# pca9306_9dof.net
KiCad netlist of a schematic drawn in EAGLE
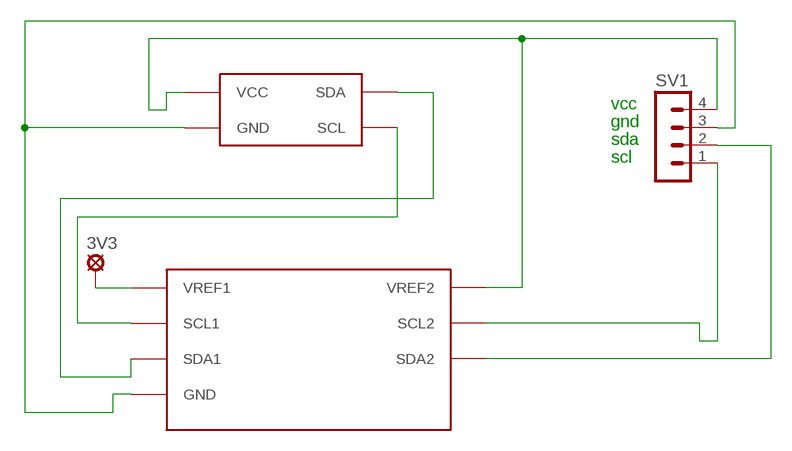
[diagram p0: schematic, sheet 1]

(export (version "E")
  (design (tool "Eeschema 10.0.6"))
  (components
    (comp (ref "3V3")
      (value "LSP11")
      (footprint "eagle-import:LSP11")
      (libsource (lib "eagle-import") (part "LSP11"))
    )
    (comp (ref "SV1")
      (value "MA04-1")
      (footprint "eagle-import:MA04-1")
      (libsource (lib "eagle-import") (part "MA04-1"))
    )
    (comp (ref "U$1")
      (value "PCA9306")
      (footprint "eagle-import:PCA9306")
      (libsource (lib "eagle-import") (part "PCA9306"))
    )
    (comp (ref "U$2")
      (value "9DOF")
      (footprint "eagle-import:9DOF")
      (libsource (lib "eagle-import") (part "9DOF"))
    )
  )
  (nets
    (net (code "1") (name "Net-(3V3-PadMP)") (class "Default")
      (node (ref "3V3") (pin "MP") (pinfunction "MP_MP") (pintype "passive"))
      (node (ref "U$1") (pin "VREF1") (pinfunction "VREF1_VREF1") (pintype "bidirectional"))
    )
    (net (code "2") (name "Net-(SV1-Pad1)") (class "Default")
      (node (ref "SV1") (pin "1") (pinfunction "1_1") (pintype "passive"))
      (node (ref "U$1") (pin "SCL2") (pinfunction "SCL2_SCL2") (pintype "bidirectional"))
    )
    (net (code "3") (name "Net-(SV1-Pad2)") (class "Default")
      (node (ref "SV1") (pin "2") (pinfunction "2_2") (pintype "passive"))
      (node (ref "U$1") (pin "SDA2") (pinfunction "SDA2_SDA2") (pintype "bidirectional"))
    )
    (net (code "4") (name "Net-(SV1-Pad3)") (class "Default")
      (node (ref "SV1") (pin "3") (pinfunction "3_3") (pintype "passive"))
      (node (ref "U$1") (pin "GND") (pinfunction "GND_GND") (pintype "bidirectional"))
      (node (ref "U$2") (pin "GND") (pinfunction "GND_GND") (pintype "bidirectional"))
    )
    (net (code "5") (name "Net-(SV1-Pad4)") (class "Default")
      (node (ref "SV1") (pin "4") (pinfunction "4_4") (pintype "passive"))
      (node (ref "U$1") (pin "VREF2") (pinfunction "VREF2_VREF2") (pintype "bidirectional"))
      (node (ref "U$2") (pin "VCC") (pinfunction "VCC_VCC") (pintype "bidirectional"))
    )
    (net (code "6") (name "Net-(U$1-PadSCL1)") (class "Default")
      (node (ref "U$1") (pin "SCL1") (pinfunction "SCL1_SCL1") (pintype "bidirectional"))
      (node (ref "U$2") (pin "SCL") (pinfunction "SCL_SCL") (pintype "bidirectional"))
    )
    (net (code "7") (name "Net-(U$1-PadSDA1)") (class "Default")
      (node (ref "U$1") (pin "SDA1") (pinfunction "SDA1_SDA1") (pintype "bidirectional"))
      (node (ref "U$2") (pin "SDA") (pinfunction "SDA_SDA") (pintype "bidirectional"))
    )
  )
)
